# Mac_Project_sch_With_Resistors.net
KiCad netlist of a schematic drawn in EAGLE
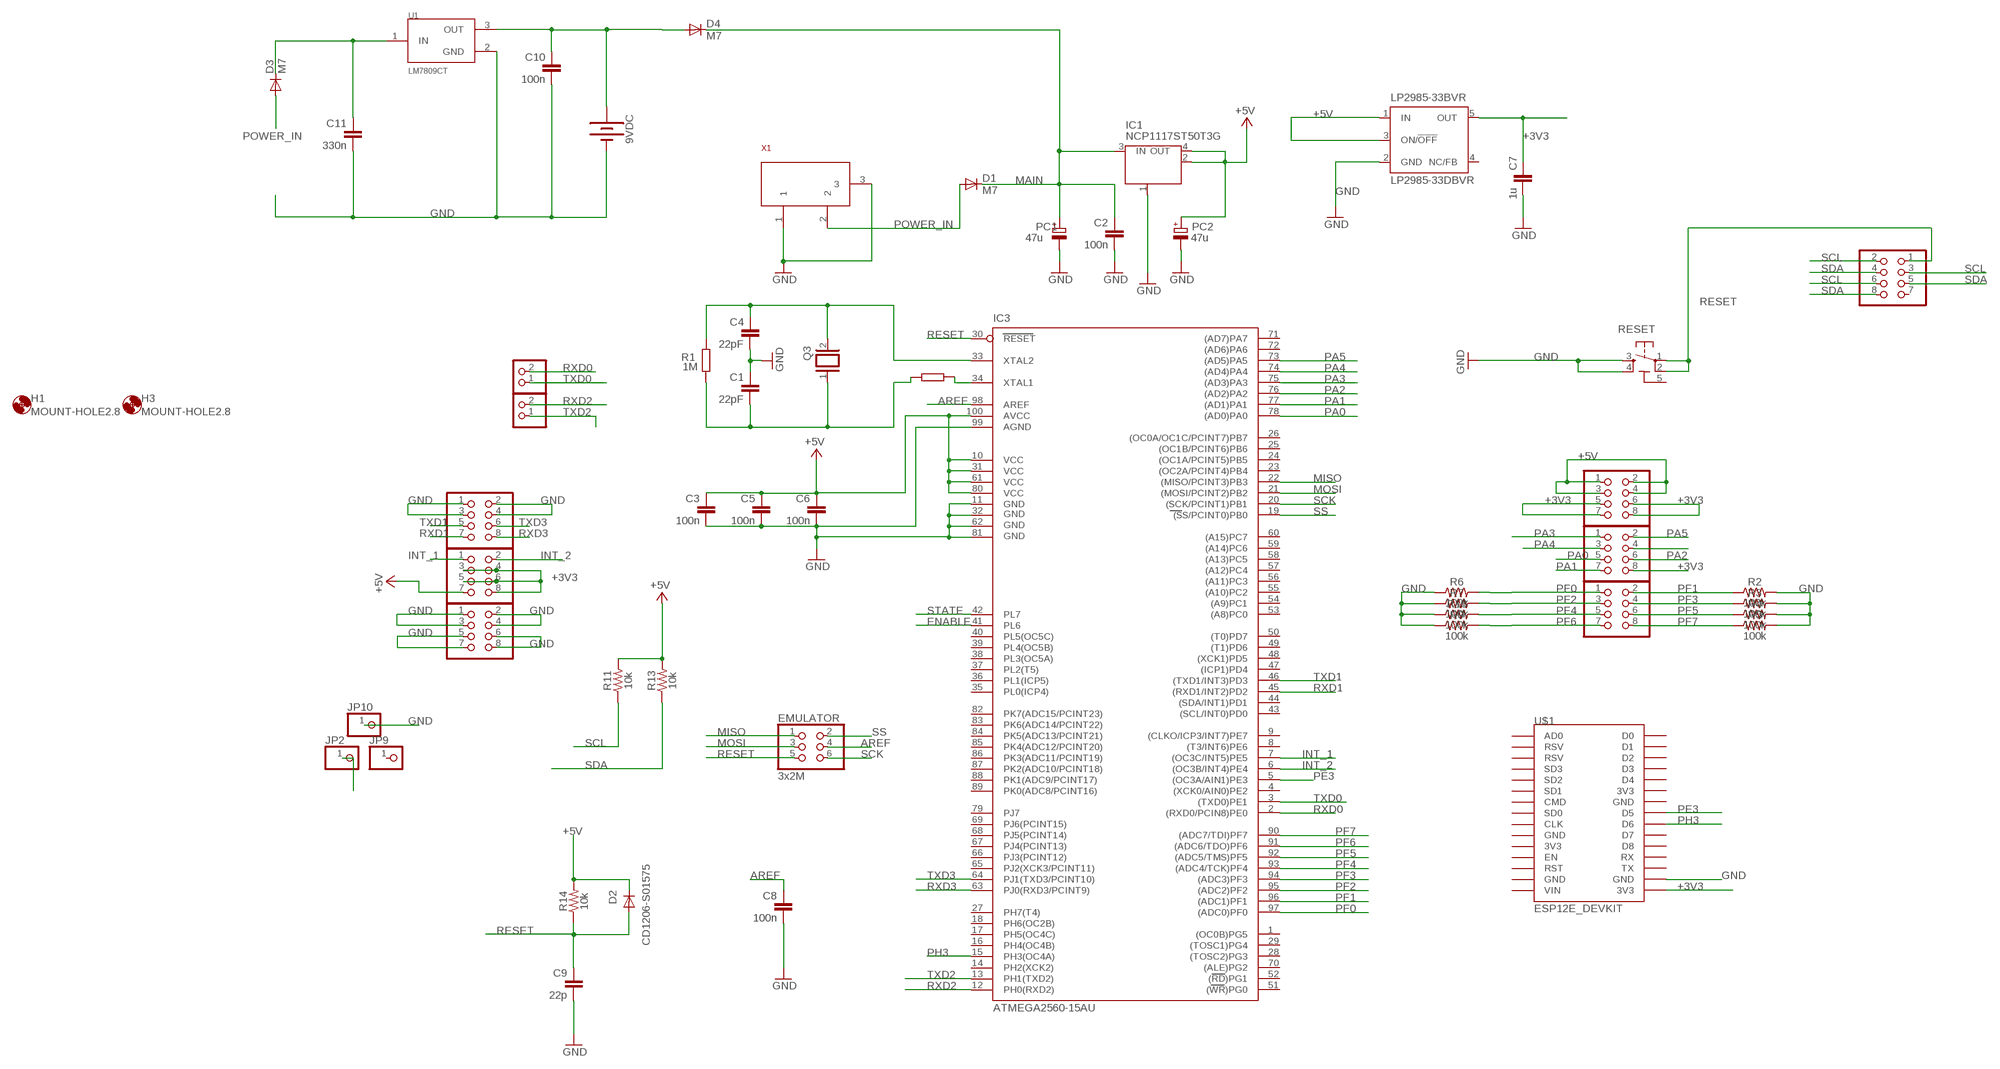
[diagram p0: schematic, sheet 1]

(export (version "E")
  (design (tool "Eeschema 10.0.6"))
  (components
    (comp (ref "1X1")
      (value "1x2")
      (footprint "eagle-import:1X02")
      (libsource (lib "eagle-import") (part "PINHD-1X2"))
    )
    (comp (ref "1X2")
      (value "1x2")
      (footprint "eagle-import:1X02")
      (libsource (lib "eagle-import") (part "PINHD-1X2"))
    )
    (comp (ref "9VDC")
      (value "BATTERY-9V")
      (footprint "eagle-import:BATTCON_9V")
      (libsource (lib "eagle-import") (part "BATTERY-9V"))
    )
    (comp (ref "C1")
      (value "22pF")
      (footprint "eagle-import:C0603-ROUND")
      (libsource (lib "eagle-import") (part "C-EU0603-RND"))
    )
    (comp (ref "C2")
      (value "100n")
      (footprint "eagle-import:C0603-ROUND")
      (libsource (lib "eagle-import") (part "C-EU0603-RND"))
    )
    (comp (ref "C3")
      (value "100n")
      (footprint "eagle-import:C0603-ROUND")
      (libsource (lib "eagle-import") (part "C-EU0603-RND"))
    )
    (comp (ref "C4")
      (value "22pF")
      (footprint "eagle-import:C0603-ROUND")
      (libsource (lib "eagle-import") (part "C-EU0603-RND"))
    )
    (comp (ref "C5")
      (value "100n")
      (footprint "eagle-import:C0603-ROUND")
      (libsource (lib "eagle-import") (part "C-EU0603-RND"))
    )
    (comp (ref "C6")
      (value "100n")
      (footprint "eagle-import:C0603-ROUND")
      (libsource (lib "eagle-import") (part "C-EU0603-RND"))
    )
    (comp (ref "C7")
      (value "1u")
      (footprint "eagle-import:C0603-ROUND")
      (libsource (lib "eagle-import") (part "C-EU0603-RND"))
    )
    (comp (ref "C8")
      (value "100n")
      (footprint "eagle-import:C0603-ROUND")
      (libsource (lib "eagle-import") (part "C-EU0603-RND"))
    )
    (comp (ref "C9")
      (value "22p")
      (footprint "eagle-import:C0603-ROUND")
      (libsource (lib "eagle-import") (part "C-EU0603-RND"))
    )
    (comp (ref "C10")
      (value "100n")
      (footprint "eagle-import:C0603-ROUND")
      (libsource (lib "eagle-import") (part "C-EU0603-RND"))
    )
    (comp (ref "C11")
      (value "330n")
      (footprint "eagle-import:C0603-ROUND")
      (libsource (lib "eagle-import") (part "C-EU0603-RND"))
    )
    (comp (ref "D1")
      (value "M7")
      (footprint "eagle-import:SMB")
      (libsource (lib "eagle-import") (part "DIODE-SMB"))
    )
    (comp (ref "D2")
      (value "CD1206-S01575")
      (footprint "eagle-import:MINIMELF")
      (libsource (lib "eagle-import") (part "DIODE-MINIMELF"))
    )
    (comp (ref "D3")
      (value "M7")
      (footprint "eagle-import:SMB")
      (libsource (lib "eagle-import") (part "DIODE-SMB"))
    )
    (comp (ref "D4")
      (value "M7")
      (footprint "eagle-import:SMB")
      (libsource (lib "eagle-import") (part "DIODE-SMB"))
    )
    (comp (ref "EMULATOR")
      (value "3x2M")
      (footprint "eagle-import:2X03")
      (libsource (lib "eagle-import") (part "PINHD-2X3"))
    )
    (comp (ref "H1")
      (value "MOUNT-HOLE2.8")
      (footprint "eagle-import:2,8")
      (libsource (lib "eagle-import") (part "MOUNT-HOLE2.8"))
    )
    (comp (ref "H3")
      (value "MOUNT-HOLE2.8")
      (footprint "eagle-import:2,8")
      (libsource (lib "eagle-import") (part "MOUNT-HOLE2.8"))
    )
    (comp (ref "IC1")
      (value "NCP1117ST50T3G")
      (footprint "eagle-import:SOT223")
      (libsource (lib "eagle-import") (part "MC33269ST-3.3T3"))
    )
    (comp (ref "IC3")
      (value "ATMEGA2560-15AU")
      (footprint "eagle-import:TQFP100")
      (fields (field (name "PART_NUMBER") "ATMEGA2560-16AU"))
      (libsource (lib "eagle-import") (part "0023_ATMEGA2560-16AU"))
    )
    (comp (ref "JP1")
      (value "PINHD-2X4")
      (footprint "eagle-import:2X04")
      (libsource (lib "eagle-import") (part "PINHD-2X4"))
    )
    (comp (ref "JP2")
      (value "PINHD-1X1")
      (footprint "eagle-import:1X01")
      (libsource (lib "eagle-import") (part "PINHD-1X1"))
    )
    (comp (ref "JP3")
      (value "PINHD-2X4")
      (footprint "eagle-import:2X04")
      (libsource (lib "eagle-import") (part "PINHD-2X4"))
    )
    (comp (ref "JP4")
      (value "PINHD-2X4")
      (footprint "eagle-import:2X04")
      (libsource (lib "eagle-import") (part "PINHD-2X4"))
    )
    (comp (ref "JP5")
      (value "PINHD-2X4")
      (footprint "eagle-import:2X04")
      (libsource (lib "eagle-import") (part "PINHD-2X4"))
    )
    (comp (ref "JP6")
      (value "PINHD-2X4")
      (footprint "eagle-import:2X04")
      (libsource (lib "eagle-import") (part "PINHD-2X4"))
    )
    (comp (ref "JP7")
      (value "PINHD-2X4")
      (footprint "eagle-import:2X04")
      (libsource (lib "eagle-import") (part "PINHD-2X4"))
    )
    (comp (ref "JP8")
      (value "PINHD-2X4")
      (footprint "eagle-import:2X04")
      (libsource (lib "eagle-import") (part "PINHD-2X4"))
    )
    (comp (ref "JP9")
      (value "PINHD-1X1")
      (footprint "eagle-import:1X01")
      (libsource (lib "eagle-import") (part "PINHD-1X1"))
    )
    (comp (ref "JP10")
      (value "PINHD-1X1")
      (footprint "eagle-import:1X01")
      (libsource (lib "eagle-import") (part "PINHD-1X1"))
    )
    (comp (ref "LP2985-33BVR")
      (value "LP2985-33DBVR")
      (footprint "eagle-import:SOT23-DBV")
      (libsource (lib "eagle-import") (part "LP2985-XXDBVR33"))
    )
    (comp (ref "PC1")
      (value "47u")
      (footprint "eagle-import:PANASONIC_D")
      (libsource (lib "eagle-import") (part "CPOL-EUD"))
    )
    (comp (ref "PC2")
      (value "47u")
      (footprint "eagle-import:PANASONIC_D")
      (libsource (lib "eagle-import") (part "CPOL-EUD"))
    )
    (comp (ref "Q3")
      (value "16MHz")
      (footprint "eagle-import:QS")
      (libsource (lib "eagle-import") (part "XTAL/S"))
    )
    (comp (ref "R1")
      (value "1M")
      (footprint "eagle-import:R0603-ROUND")
      (libsource (lib "eagle-import") (part "R-EU_R0603"))
    )
    (comp (ref "R2")
      (value "100k")
      (footprint "eagle-import:0603")
      (libsource (lib "eagle-import") (part "100KOHM-0603-1/10W-1%"))
    )
    (comp (ref "R3")
      (value "100k")
      (footprint "eagle-import:0603")
      (libsource (lib "eagle-import") (part "100KOHM-0603-1/10W-1%"))
    )
    (comp (ref "R4")
      (value "100k")
      (footprint "eagle-import:0603")
      (libsource (lib "eagle-import") (part "100KOHM-0603-1/10W-1%"))
    )
    (comp (ref "R5")
      (value "100k")
      (footprint "eagle-import:0603")
      (libsource (lib "eagle-import") (part "100KOHM-0603-1/10W-1%"))
    )
    (comp (ref "R6")
      (value "100k")
      (footprint "eagle-import:0603")
      (libsource (lib "eagle-import") (part "100KOHM-0603-1/10W-1%"))
    )
    (comp (ref "R7")
      (value "100k")
      (footprint "eagle-import:0603")
      (libsource (lib "eagle-import") (part "100KOHM-0603-1/10W-1%"))
    )
    (comp (ref "R9")
      (value "100k")
      (footprint "eagle-import:0603")
      (libsource (lib "eagle-import") (part "100KOHM-0603-1/10W-1%"))
    )
    (comp (ref "R10")
      (value "100k")
      (footprint "eagle-import:0603")
      (libsource (lib "eagle-import") (part "100KOHM-0603-1/10W-1%"))
    )
    (comp (ref "R11")
      (value "10k")
      (footprint "eagle-import:0603")
      (libsource (lib "eagle-import") (part "10KOHM-0603-1/10W-1%"))
    )
    (comp (ref "R12")
      (value "27O")
      (footprint "eagle-import:R0603-ROUND")
      (libsource (lib "eagle-import") (part "R-EU_R0603"))
    )
    (comp (ref "R13")
      (value "10k")
      (footprint "eagle-import:0603")
      (libsource (lib "eagle-import") (part "10KOHM-0603-1/10W-1%"))
    )
    (comp (ref "R14")
      (value "10k")
      (footprint "eagle-import:0603")
      (libsource (lib "eagle-import") (part "10KOHM-0603-1/10W-1%"))
    )
    (comp (ref "RESET")
      (value "TS42")
      (footprint "eagle-import:TS42")
      (libsource (lib "eagle-import") (part "TS42"))
    )
    (comp (ref "U$1")
      (value "ESP12E_DEVKIT")
      (footprint "eagle-import:ESP12E_DEVKIT")
      (libsource (lib "eagle-import") (part "ESP12E_DEVKIT"))
    )
    (comp (ref "U1")
      (value "LM7809CT")
      (footprint "eagle-import:TO254P470X1016X1879-3P")
      (fields (field (name "MF") "ON Semiconductor"))
      (libsource (lib "eagle-import") (part "LM7809CT"))
    )
    (comp (ref "X1")
      (value "POWERSUPPLY_DC21MMX")
      (footprint "eagle-import:POWERSUPPLY_DC-21MM")
      (libsource (lib "eagle-import") (part "POWERSUPPLY_DC21MMX"))
    )
  )
  (nets
    (net (code "1") (name "+5V") (class "Default")
      (node (ref "C3") (pin "1") (pinfunction "1_1") (pintype "passive"))
      (node (ref "C5") (pin "1") (pinfunction "1_1") (pintype "passive"))
      (node (ref "C6") (pin "1") (pinfunction "1_1") (pintype "passive"))
      (node (ref "D2") (pin "C") (pinfunction "C_C") (pintype "passive"))
      (node (ref "IC1") (pin "2") (pinfunction "OUT_2") (pintype "passive"))
      (node (ref "IC1") (pin "4") (pinfunction "OUT_4") (pintype "passive"))
      (node (ref "IC3") (pin "10") (pinfunction "VCC_10") (pintype "power_in"))
      (node (ref "IC3") (pin "100") (pinfunction "AVCC_100") (pintype "power_in"))
      (node (ref "IC3") (pin "31") (pinfunction "VCC1_31") (pintype "power_in"))
      (node (ref "IC3") (pin "61") (pinfunction "VCC2_61") (pintype "power_in"))
      (node (ref "IC3") (pin "80") (pinfunction "VCC3_80") (pintype "power_in"))
      (node (ref "JP3") (pin "1") (pinfunction "1_1") (pintype "passive"))
      (node (ref "JP3") (pin "2") (pinfunction "2_2") (pintype "passive"))
      (node (ref "JP3") (pin "3") (pinfunction "3_3") (pintype "passive"))
      (node (ref "JP3") (pin "4") (pinfunction "4_4") (pintype "passive"))
      (node (ref "JP7") (pin "7") (pinfunction "7_7") (pintype "passive"))
      (node (ref "LP2985-33BVR") (pin "1") (pinfunction "IN_1") (pintype "input"))
      (node (ref "LP2985-33BVR") (pin "3") (pinfunction "ON/~{OFF}_3") (pintype "input"))
      (node (ref "PC2") (pin "+") (pinfunction "+_+") (pintype "passive"))
      (node (ref "R11") (pin "2") (pinfunction "2_2") (pintype "passive"))
      (node (ref "R13") (pin "2") (pinfunction "2_2") (pintype "passive"))
      (node (ref "R14") (pin "2") (pinfunction "2_2") (pintype "passive"))
    )
    (net (code "2") (name "/+3V3") (class "Default")
      (node (ref "C7") (pin "2") (pinfunction "2_2") (pintype "passive"))
      (node (ref "JP3") (pin "5") (pinfunction "5_5") (pintype "passive"))
      (node (ref "JP3") (pin "6") (pinfunction "6_6") (pintype "passive"))
      (node (ref "JP3") (pin "7") (pinfunction "7_7") (pintype "passive"))
      (node (ref "JP3") (pin "8") (pinfunction "8_8") (pintype "passive"))
      (node (ref "JP4") (pin "8") (pinfunction "8_8") (pintype "passive"))
      (node (ref "JP7") (pin "3") (pinfunction "3_3") (pintype "passive"))
      (node (ref "JP7") (pin "4") (pinfunction "4_4") (pintype "passive"))
      (node (ref "JP7") (pin "5") (pinfunction "5_5") (pintype "passive"))
      (node (ref "JP7") (pin "6") (pinfunction "6_6") (pintype "passive"))
      (node (ref "JP7") (pin "8") (pinfunction "8_8") (pintype "passive"))
      (node (ref "LP2985-33BVR") (pin "5") (pinfunction "OUT_5") (pintype "passive"))
      (node (ref "U$1") (pin "3V3@2") (pinfunction "3V3_3V3@2") (pintype "bidirectional"))
    )
    (net (code "3") (name "/5-GND") (class "Default")
      (node (ref "RESET") (pin "5") (pinfunction "5-GND_5") (pintype "power_in"))
    )
    (net (code "4") (name "/AREF") (class "Default")
      (node (ref "C8") (pin "1") (pinfunction "1_1") (pintype "passive"))
      (node (ref "EMULATOR") (pin "4") (pinfunction "4_4") (pintype "passive"))
      (node (ref "IC3") (pin "98") (pinfunction "AREF_98") (pintype "bidirectional"))
    )
    (net (code "5") (name "/ENABLE") (class "Default")
      (node (ref "IC3") (pin "41") (pinfunction "PL6_41") (pintype "bidirectional"))
    )
    (net (code "6") (name "/INT_1") (class "Default")
      (node (ref "IC3") (pin "7") (pinfunction "(OC3C/INT5)PE5_7") (pintype "bidirectional"))
      (node (ref "JP7") (pin "1") (pinfunction "1_1") (pintype "passive"))
    )
    (net (code "7") (name "/INT_2") (class "Default")
      (node (ref "IC3") (pin "6") (pinfunction "(OC3B/INT4)PE4_6") (pintype "bidirectional"))
      (node (ref "JP7") (pin "2") (pinfunction "2_2") (pintype "passive"))
    )
    (net (code "8") (name "/MAIN") (class "Default")
      (node (ref "C2") (pin "1") (pinfunction "1_1") (pintype "passive"))
      (node (ref "D1") (pin "C") (pinfunction "C_C") (pintype "passive"))
      (node (ref "D4") (pin "C") (pinfunction "C_C") (pintype "passive"))
      (node (ref "IC1") (pin "3") (pinfunction "IN_3") (pintype "input"))
      (node (ref "PC1") (pin "+") (pinfunction "+_+") (pintype "passive"))
    )
    (net (code "9") (name "/MISO") (class "Default")
      (node (ref "EMULATOR") (pin "1") (pinfunction "1_1") (pintype "passive"))
      (node (ref "IC3") (pin "22") (pinfunction "(MISO/PCINT3)PB3_22") (pintype "bidirectional"))
    )
    (net (code "10") (name "/MOSI") (class "Default")
      (node (ref "EMULATOR") (pin "3") (pinfunction "3_3") (pintype "passive"))
      (node (ref "IC3") (pin "21") (pinfunction "(MOSI/PCINT2)PB2_21") (pintype "bidirectional"))
    )
    (net (code "11") (name "/PA0") (class "Default")
      (node (ref "IC3") (pin "78") (pinfunction "(AD0)PA0_78") (pintype "bidirectional"))
      (node (ref "JP4") (pin "5") (pinfunction "5_5") (pintype "passive"))
    )
    (net (code "12") (name "/PA1") (class "Default")
      (node (ref "IC3") (pin "77") (pinfunction "(AD1)PA1_77") (pintype "bidirectional"))
      (node (ref "JP4") (pin "7") (pinfunction "7_7") (pintype "passive"))
    )
    (net (code "13") (name "/PA2") (class "Default")
      (node (ref "IC3") (pin "76") (pinfunction "(AD2)PA2_76") (pintype "bidirectional"))
      (node (ref "JP4") (pin "6") (pinfunction "6_6") (pintype "passive"))
    )
    (net (code "14") (name "/PA3") (class "Default")
      (node (ref "IC3") (pin "75") (pinfunction "(AD3)PA3_75") (pintype "bidirectional"))
      (node (ref "JP4") (pin "1") (pinfunction "1_1") (pintype "passive"))
    )
    (net (code "15") (name "/PA4") (class "Default")
      (node (ref "IC3") (pin "74") (pinfunction "(AD4)PA4_74") (pintype "bidirectional"))
      (node (ref "JP4") (pin "3") (pinfunction "3_3") (pintype "passive"))
    )
    (net (code "16") (name "/PA5") (class "Default")
      (node (ref "IC3") (pin "73") (pinfunction "(AD5)PA5_73") (pintype "bidirectional"))
      (node (ref "JP4") (pin "2") (pinfunction "2_2") (pintype "passive"))
    )
    (net (code "17") (name "/PE3") (class "Default")
      (node (ref "IC3") (pin "5") (pinfunction "(OC3A/AIN1)PE3_5") (pintype "bidirectional"))
      (node (ref "U$1") (pin "D5") (pinfunction "D5_D5") (pintype "bidirectional"))
    )
    (net (code "18") (name "/PF0") (class "Default")
      (node (ref "IC3") (pin "97") (pinfunction "(ADC0)PF0_97") (pintype "bidirectional"))
      (node (ref "JP8") (pin "1") (pinfunction "1_1") (pintype "passive"))
      (node (ref "R6") (pin "2") (pinfunction "2_2") (pintype "passive"))
    )
    (net (code "19") (name "/PF1") (class "Default")
      (node (ref "IC3") (pin "96") (pinfunction "(ADC1)PF1_96") (pintype "bidirectional"))
      (node (ref "JP8") (pin "2") (pinfunction "2_2") (pintype "passive"))
      (node (ref "R2") (pin "1") (pinfunction "1_1") (pintype "passive"))
    )
    (net (code "20") (name "/PF2") (class "Default")
      (node (ref "IC3") (pin "95") (pinfunction "(ADC2)PF2_95") (pintype "bidirectional"))
      (node (ref "JP8") (pin "3") (pinfunction "3_3") (pintype "passive"))
      (node (ref "R7") (pin "2") (pinfunction "2_2") (pintype "passive"))
    )
    (net (code "21") (name "/PF3") (class "Default")
      (node (ref "IC3") (pin "94") (pinfunction "(ADC3)PF3_94") (pintype "bidirectional"))
      (node (ref "JP8") (pin "4") (pinfunction "4_4") (pintype "passive"))
      (node (ref "R3") (pin "1") (pinfunction "1_1") (pintype "passive"))
    )
    (net (code "22") (name "/PF4") (class "Default")
      (node (ref "IC3") (pin "93") (pinfunction "(ADC4/TCK)PF4_93") (pintype "bidirectional"))
      (node (ref "JP8") (pin "5") (pinfunction "5_5") (pintype "passive"))
      (node (ref "R10") (pin "2") (pinfunction "2_2") (pintype "passive"))
    )
    (net (code "23") (name "/PF5") (class "Default")
      (node (ref "IC3") (pin "92") (pinfunction "(ADC5/TMS)PF5_92") (pintype "bidirectional"))
      (node (ref "JP8") (pin "6") (pinfunction "6_6") (pintype "passive"))
      (node (ref "R4") (pin "1") (pinfunction "1_1") (pintype "passive"))
    )
    (net (code "24") (name "/PF6") (class "Default")
      (node (ref "IC3") (pin "91") (pinfunction "(ADC6/TDO)PF6_91") (pintype "bidirectional"))
      (node (ref "JP8") (pin "7") (pinfunction "7_7") (pintype "passive"))
      (node (ref "R9") (pin "2") (pinfunction "2_2") (pintype "passive"))
    )
    (net (code "25") (name "/PF7") (class "Default")
      (node (ref "IC3") (pin "90") (pinfunction "(ADC7/TDI)PF7_90") (pintype "bidirectional"))
      (node (ref "JP8") (pin "8") (pinfunction "8_8") (pintype "passive"))
      (node (ref "R5") (pin "1") (pinfunction "1_1") (pintype "passive"))
    )
    (net (code "26") (name "/PH3") (class "Default")
      (node (ref "IC3") (pin "15") (pinfunction "PH3(OC4A)_15") (pintype "bidirectional"))
      (node (ref "U$1") (pin "D6") (pinfunction "D6_D6") (pintype "bidirectional"))
    )
    (net (code "27") (name "/POWER_IN") (class "Default")
      (node (ref "D1") (pin "A") (pinfunction "A_A") (pintype "passive"))
      (node (ref "D3") (pin "A") (pinfunction "A_A") (pintype "passive"))
      (node (ref "X1") (pin "2") (pinfunction "2_2") (pintype "power_in"))
    )
    (net (code "28") (name "/RESET") (class "Default")
      (node (ref "C9") (pin "1") (pinfunction "1_1") (pintype "passive"))
      (node (ref "D2") (pin "A") (pinfunction "A_A") (pintype "passive"))
      (node (ref "EMULATOR") (pin "5") (pinfunction "5_5") (pintype "passive"))
      (node (ref "IC3") (pin "30") (pinfunction "RESET_30") (pintype "input"))
      (node (ref "JP5") (pin "1") (pinfunction "1_1") (pintype "passive"))
      (node (ref "R14") (pin "1") (pinfunction "1_1") (pintype "passive"))
      (node (ref "RESET") (pin "1") (pinfunction "1_1") (pintype "passive"))
      (node (ref "RESET") (pin "2") (pinfunction "2_2") (pintype "passive"))
    )
    (net (code "29") (name "/RXD0") (class "Default")
      (node (ref "1X2") (pin "2") (pinfunction "2_2") (pintype "passive"))
      (node (ref "IC3") (pin "2") (pinfunction "(RXD0/PCIN8)PE0_2") (pintype "bidirectional"))
    )
    (net (code "30") (name "/RXD1") (class "Default")
      (node (ref "IC3") (pin "45") (pinfunction "(RXD1/INT2)PD2_45") (pintype "bidirectional"))
      (node (ref "JP6") (pin "7") (pinfunction "7_7") (pintype "passive"))
    )
    (net (code "31") (name "/RXD2") (class "Default")
      (node (ref "1X1") (pin "2") (pinfunction "2_2") (pintype "passive"))
      (node (ref "IC3") (pin "12") (pinfunction "PH0(RXD2)_12") (pintype "bidirectional"))
    )
    (net (code "32") (name "/RXD3") (class "Default")
      (node (ref "IC3") (pin "63") (pinfunction "PJ0(RXD3/PCINT9)_63") (pintype "bidirectional"))
      (node (ref "JP6") (pin "8") (pinfunction "8_8") (pintype "passive"))
    )
    (net (code "33") (name "/SCK") (class "Default")
      (node (ref "EMULATOR") (pin "6") (pinfunction "6_6") (pintype "passive"))
      (node (ref "IC3") (pin "20") (pinfunction "(SCK/PCINT1)PB1_20") (pintype "bidirectional"))
    )
    (net (code "34") (name "/SCL") (class "Default")
      (node (ref "JP5") (pin "2") (pinfunction "2_2") (pintype "passive"))
      (node (ref "JP5") (pin "3") (pinfunction "3_3") (pintype "passive"))
      (node (ref "JP5") (pin "6") (pinfunction "6_6") (pintype "passive"))
      (node (ref "R11") (pin "1") (pinfunction "1_1") (pintype "passive"))
    )
    (net (code "35") (name "/SDA") (class "Default")
      (node (ref "JP5") (pin "4") (pinfunction "4_4") (pintype "passive"))
      (node (ref "JP5") (pin "5") (pinfunction "5_5") (pintype "passive"))
      (node (ref "JP5") (pin "8") (pinfunction "8_8") (pintype "passive"))
      (node (ref "R13") (pin "1") (pinfunction "1_1") (pintype "passive"))
    )
    (net (code "36") (name "/SS") (class "Default")
      (node (ref "EMULATOR") (pin "2") (pinfunction "2_2") (pintype "passive"))
      (node (ref "IC3") (pin "19") (pinfunction "(SS/PCINT0)PB0_19") (pintype "bidirectional"))
    )
    (net (code "37") (name "/STATE") (class "Default")
      (node (ref "IC3") (pin "42") (pinfunction "PL7_42") (pintype "bidirectional"))
    )
    (net (code "38") (name "/TXD0") (class "Default")
      (node (ref "1X2") (pin "1") (pinfunction "1_1") (pintype "passive"))
      (node (ref "IC3") (pin "3") (pinfunction "(TXD0)PE1_3") (pintype "bidirectional"))
    )
    (net (code "39") (name "/TXD1") (class "Default")
      (node (ref "IC3") (pin "46") (pinfunction "(TXD1/INT3)PD3_46") (pintype "bidirectional"))
      (node (ref "JP6") (pin "5") (pinfunction "5_5") (pintype "passive"))
    )
    (net (code "40") (name "/TXD2") (class "Default")
      (node (ref "1X1") (pin "1") (pinfunction "1_1") (pintype "passive"))
      (node (ref "IC3") (pin "13") (pinfunction "PH1(TXD2)_13") (pintype "bidirectional"))
    )
    (net (code "41") (name "/TXD3") (class "Default")
      (node (ref "IC3") (pin "64") (pinfunction "PJ1(TXD3/PCINT10)_64") (pintype "bidirectional"))
      (node (ref "JP6") (pin "6") (pinfunction "6_6") (pintype "passive"))
    )
    (net (code "42") (name "GND") (class "Default")
      (node (ref "9VDC") (pin "-") (pinfunction "-_-") (pintype "power_in"))
      (node (ref "C1") (pin "1") (pinfunction "1_1") (pintype "passive"))
      (node (ref "C10") (pin "2") (pinfunction "2_2") (pintype "passive"))
      (node (ref "C11") (pin "2") (pinfunction "2_2") (pintype "passive"))
      (node (ref "C2") (pin "2") (pinfunction "2_2") (pintype "passive"))
      (node (ref "C3") (pin "2") (pinfunction "2_2") (pintype "passive"))
      (node (ref "C4") (pin "2") (pinfunction "2_2") (pintype "passive"))
      (node (ref "C5") (pin "2") (pinfunction "2_2") (pintype "passive"))
      (node (ref "C6") (pin "2") (pinfunction "2_2") (pintype "passive"))
      (node (ref "C7") (pin "1") (pinfunction "1_1") (pintype "passive"))
      (node (ref "C8") (pin "2") (pinfunction "2_2") (pintype "passive"))
      (node (ref "C9") (pin "2") (pinfunction "2_2") (pintype "passive"))
      (node (ref "IC1") (pin "1") (pinfunction "GND/ADJ_1") (pintype "input"))
      (node (ref "IC3") (pin "11") (pinfunction "GND_11") (pintype "power_in"))
      (node (ref "IC3") (pin "32") (pinfunction "GND1_32") (pintype "power_in"))
      (node (ref "IC3") (pin "62") (pinfunction "GND2_62") (pintype "power_in"))
      (node (ref "IC3") (pin "81") (pinfunction "GND3_81") (pintype "power_in"))
      (node (ref "IC3") (pin "99") (pinfunction "AGND_99") (pintype "power_in"))
      (node (ref "JP1") (pin "1") (pinfunction "1_1") (pintype "passive"))
      (node (ref "JP1") (pin "2") (pinfunction "2_2") (pintype "passive"))
      (node (ref "JP1") (pin "3") (pinfunction "3_3") (pintype "passive"))
      (node (ref "JP1") (pin "4") (pinfunction "4_4") (pintype "passive"))
      (node (ref "JP1") (pin "5") (pinfunction "5_5") (pintype "passive"))
      (node (ref "JP1") (pin "6") (pinfunction "6_6") (pintype "passive"))
      (node (ref "JP1") (pin "7") (pinfunction "7_7") (pintype "passive"))
      (node (ref "JP1") (pin "8") (pinfunction "8_8") (pintype "passive"))
      (node (ref "JP10") (pin "1") (pinfunction "1_1") (pintype "passive"))
      (node (ref "JP4") (pin "4") (pinfunction "4_4") (pintype "passive"))
      (node (ref "JP6") (pin "1") (pinfunction "1_1") (pintype "passive"))
      (node (ref "JP6") (pin "2") (pinfunction "2_2") (pintype "passive"))
      (node (ref "JP6") (pin "3") (pinfunction "3_3") (pintype "passive"))
      (node (ref "JP6") (pin "4") (pinfunction "4_4") (pintype "passive"))
      (node (ref "LP2985-33BVR") (pin "2") (pinfunction "GND_2") (pintype "power_in"))
      (node (ref "PC1") (pin "-") (pinfunction "-_-") (pintype "passive"))
      (node (ref "PC2") (pin "-") (pinfunction "-_-") (pintype "passive"))
      (node (ref "R10") (pin "1") (pinfunction "1_1") (pintype "passive"))
      (node (ref "R2") (pin "2") (pinfunction "2_2") (pintype "passive"))
      (node (ref "R3") (pin "2") (pinfunction "2_2") (pintype "passive"))
      (node (ref "R4") (pin "2") (pinfunction "2_2") (pintype "passive"))
      (node (ref "R5") (pin "2") (pinfunction "2_2") (pintype "passive"))
      (node (ref "R6") (pin "1") (pinfunction "1_1") (pintype "passive"))
      (node (ref "R7") (pin "1") (pinfunction "1_1") (pintype "passive"))
      (node (ref "R9") (pin "1") (pinfunction "1_1") (pintype "passive"))
      (node (ref "RESET") (pin "3") (pinfunction "3_3") (pintype "passive"))
      (node (ref "RESET") (pin "4") (pinfunction "4_4") (pintype "passive"))
      (node (ref "U$1") (pin "GND@3") (pinfunction "GND_GND@3") (pintype "bidirectional"))
      (node (ref "U1") (pin "2") (pinfunction "GND_2") (pintype "power_in"))
      (node (ref "X1") (pin "1") (pinfunction "1_1") (pintype "power_in"))
      (node (ref "X1") (pin "3") (pinfunction "3_3") (pintype "power_in"))
    )
    (net (code "43") (name "Net-(C1-Pad2)") (class "Default")
      (node (ref "C1") (pin "2") (pinfunction "2_2") (pintype "passive"))
      (node (ref "Q3") (pin "1") (pinfunction "1_1") (pintype "passive"))
      (node (ref "R1") (pin "1") (pinfunction "1_1") (pintype "passive"))
      (node (ref "R12") (pin "1") (pinfunction "1_1") (pintype "passive"))
    )
    (net (code "44") (name "Net-(IC3-XTAL1)") (class "Default")
      (node (ref "IC3") (pin "34") (pinfunction "XTAL1_34") (pintype "input"))
      (node (ref "R12") (pin "2") (pinfunction "2_2") (pintype "passive"))
    )
    (net (code "45") (name "Net-(IC3-XTAL2)") (class "Default")
      (node (ref "C4") (pin "1") (pinfunction "1_1") (pintype "passive"))
      (node (ref "IC3") (pin "33") (pinfunction "XTAL2_33") (pintype "output"))
      (node (ref "Q3") (pin "2") (pinfunction "2_2") (pintype "passive"))
      (node (ref "R1") (pin "2") (pinfunction "2_2") (pintype "passive"))
    )
    (net (code "46") (name "Net-(U1-IN)") (class "Default")
      (node (ref "C11") (pin "1") (pinfunction "1_1") (pintype "passive"))
      (node (ref "D3") (pin "C") (pinfunction "C_C") (pintype "passive"))
      (node (ref "U1") (pin "1") (pinfunction "IN_1") (pintype "input"))
    )
    (net (code "47") (name "Net-(U1-OUT)") (class "Default")
      (node (ref "9VDC") (pin "+") (pinfunction "+_+") (pintype "power_in"))
      (node (ref "C10") (pin "1") (pinfunction "1_1") (pintype "passive"))
      (node (ref "D4") (pin "A") (pinfunction "A_A") (pintype "passive"))
      (node (ref "U1") (pin "3") (pinfunction "OUT_3") (pintype "output"))
    )
    (net (code "48") (name "unconnected-(IC3-(A8)PC0-Pad53)") (class "Default")
      (node (ref "IC3") (pin "53") (pinfunction "(A8)PC0_53") (pintype "bidirectional"))
    )
    (net (code "49") (name "unconnected-(IC3-(A9)PC1-Pad54)") (class "Default")
      (node (ref "IC3") (pin "54") (pinfunction "(A9)PC1_54") (pintype "bidirectional"))
    )
    (net (code "50") (name "unconnected-(IC3-(A10)PC2-Pad55)") (class "Default")
      (node (ref "IC3") (pin "55") (pinfunction "(A10)PC2_55") (pintype "bidirectional"))
    )
    (net (code "51") (name "unconnected-(IC3-(A11)PC3-Pad56)") (class "Default")
      (node (ref "IC3") (pin "56") (pinfunction "(A11)PC3_56") (pintype "bidirectional"))
    )
    (net (code "52") (name "unconnected-(IC3-(A12)PC4-Pad57)") (class "Default")
      (node (ref "IC3") (pin "57") (pinfunction "(A12)PC4_57") (pintype "bidirectional"))
    )
    (net (code "53") (name "unconnected-(IC3-(A13)PC5-Pad58)") (class "Default")
      (node (ref "IC3") (pin "58") (pinfunction "(A13)PC5_58") (pintype "bidirectional"))
    )
    (net (code "54") (name "unconnected-(IC3-(A14)PC6-Pad59)") (class "Default")
      (node (ref "IC3") (pin "59") (pinfunction "(A14)PC6_59") (pintype "bidirectional"))
    )
    (net (code "55") (name "unconnected-(IC3-(A15)PC7-Pad60)") (class "Default")
      (node (ref "IC3") (pin "60") (pinfunction "(A15)PC7_60") (pintype "bidirectional"))
    )
    (net (code "56") (name "unconnected-(IC3-(AD6)PA6-Pad72)") (class "Default")
      (node (ref "IC3") (pin "72") (pinfunction "(AD6)PA6_72") (pintype "bidirectional"))
    )
    (net (code "57") (name "unconnected-(IC3-(AD7)PA7-Pad71)") (class "Default")
      (node (ref "IC3") (pin "71") (pinfunction "(AD7)PA7_71") (pintype "bidirectional"))
    )
    (net (code "58") (name "unconnected-(IC3-(ALE)PG2-Pad70)") (class "Default")
      (node (ref "IC3") (pin "70") (pinfunction "(ALE)PG2_70") (pintype "bidirectional"))
    )
    (net (code "59") (name "unconnected-(IC3-(CLKO{slash}ICP3{slash}INT7)PE7-Pad9)") (class "Default")
      (node (ref "IC3") (pin "9") (pinfunction "(CLKO/ICP3/INT7)PE7_9") (pintype "bidirectional"))
    )
    (net (code "60") (name "unconnected-(IC3-(ICP1)PD4-Pad47)") (class "Default")
      (node (ref "IC3") (pin "47") (pinfunction "(ICP1)PD4_47") (pintype "bidirectional"))
    )
    (net (code "61") (name "unconnected-(IC3-(OC0A{slash}OC1C{slash}PCINT7)PB7-Pad26)") (class "Default")
      (node (ref "IC3") (pin "26") (pinfunction "(OC0A/OC1C/PCINT7)PB7_26") (pintype "bidirectional"))
    )
    (net (code "62") (name "unconnected-(IC3-(OC0B)PG5-Pad1)") (class "Default")
      (node (ref "IC3") (pin "1") (pinfunction "(OC0B)PG5_1") (pintype "bidirectional"))
    )
    (net (code "63") (name "unconnected-(IC3-(OC1A{slash}PCINT5)PB5-Pad24)") (class "Default")
      (node (ref "IC3") (pin "24") (pinfunction "(OC1A/PCINT5)PB5_24") (pintype "bidirectional"))
    )
    (net (code "64") (name "unconnected-(IC3-(OC1B{slash}PCINT6)PB6-Pad25)") (class "Default")
      (node (ref "IC3") (pin "25") (pinfunction "(OC1B/PCINT6)PB6_25") (pintype "bidirectional"))
    )
    (net (code "65") (name "unconnected-(IC3-(OC2A{slash}PCINT4)PB4-Pad23)") (class "Default")
      (node (ref "IC3") (pin "23") (pinfunction "(OC2A/PCINT4)PB4_23") (pintype "bidirectional"))
    )
    (net (code "66") (name "unconnected-(IC3-(RD)PG1-Pad52)") (class "Default")
      (node (ref "IC3") (pin "52") (pinfunction "(RD)PG1_52") (pintype "bidirectional"))
    )
    (net (code "67") (name "unconnected-(IC3-(SCL{slash}INT0)PD0-Pad43)") (class "Default")
      (node (ref "IC3") (pin "43") (pinfunction "(SCL/INT0)PD0_43") (pintype "bidirectional"))
    )
    (net (code "68") (name "unconnected-(IC3-(SDA{slash}INT1)PD1-Pad44)") (class "Default")
      (node (ref "IC3") (pin "44") (pinfunction "(SDA/INT1)PD1_44") (pintype "bidirectional"))
    )
    (net (code "69") (name "unconnected-(IC3-(T0)PD7-Pad50)") (class "Default")
      (node (ref "IC3") (pin "50") (pinfunction "(T0)PD7_50") (pintype "bidirectional"))
    )
    (net (code "70") (name "unconnected-(IC3-(T1)PD6-Pad49)") (class "Default")
      (node (ref "IC3") (pin "49") (pinfunction "(T1)PD6_49") (pintype "bidirectional"))
    )
    (net (code "71") (name "unconnected-(IC3-(T3{slash}INT6)PE6-Pad8)") (class "Default")
      (node (ref "IC3") (pin "8") (pinfunction "(T3/INT6)PE6_8") (pintype "bidirectional"))
    )
    (net (code "72") (name "unconnected-(IC3-(TOSC1)PG4-Pad29)") (class "Default")
      (node (ref "IC3") (pin "29") (pinfunction "(TOSC1)PG4_29") (pintype "bidirectional"))
    )
    (net (code "73") (name "unconnected-(IC3-(TOSC2)PG3-Pad28)") (class "Default")
      (node (ref "IC3") (pin "28") (pinfunction "(TOSC2)PG3_28") (pintype "bidirectional"))
    )
    (net (code "74") (name "unconnected-(IC3-(WR)PG0-Pad51)") (class "Default")
      (node (ref "IC3") (pin "51") (pinfunction "(WR)PG0_51") (pintype "bidirectional"))
    )
    (net (code "75") (name "unconnected-(IC3-(XCK0{slash}AIN0)PE2-Pad4)") (class "Default")
      (node (ref "IC3") (pin "4") (pinfunction "(XCK0/AIN0)PE2_4") (pintype "bidirectional"))
    )
    (net (code "76") (name "unconnected-(IC3-(XCK1)PD5-Pad48)") (class "Default")
      (node (ref "IC3") (pin "48") (pinfunction "(XCK1)PD5_48") (pintype "bidirectional"))
    )
    (net (code "77") (name "unconnected-(IC3-PH2(XCK2)-Pad14)") (class "Default")
      (node (ref "IC3") (pin "14") (pinfunction "PH2(XCK2)_14") (pintype "bidirectional"))
    )
    (net (code "78") (name "unconnected-(IC3-PH4(OC4B)-Pad16)") (class "Default")
      (node (ref "IC3") (pin "16") (pinfunction "PH4(OC4B)_16") (pintype "bidirectional"))
    )
    (net (code "79") (name "unconnected-(IC3-PH5(OC4C)-Pad17)") (class "Default")
      (node (ref "IC3") (pin "17") (pinfunction "PH5(OC4C)_17") (pintype "bidirectional"))
    )
    (net (code "80") (name "unconnected-(IC3-PH6(OC2B)-Pad18)") (class "Default")
      (node (ref "IC3") (pin "18") (pinfunction "PH6(OC2B)_18") (pintype "bidirectional"))
    )
    (net (code "81") (name "unconnected-(IC3-PH7(T4)-Pad27)") (class "Default")
      (node (ref "IC3") (pin "27") (pinfunction "PH7(T4)_27") (pintype "bidirectional"))
    )
    (net (code "82") (name "unconnected-(IC3-PJ2(XCK3{slash}PCINT11)-Pad65)") (class "Default")
      (node (ref "IC3") (pin "65") (pinfunction "PJ2(XCK3/PCINT11)_65") (pintype "bidirectional"))
    )
    (net (code "83") (name "unconnected-(IC3-PJ3(PCINT12)-Pad66)") (class "Default")
      (node (ref "IC3") (pin "66") (pinfunction "PJ3(PCINT12)_66") (pintype "bidirectional"))
    )
    (net (code "84") (name "unconnected-(IC3-PJ4(PCINT13)-Pad67)") (class "Default")
      (node (ref "IC3") (pin "67") (pinfunction "PJ4(PCINT13)_67") (pintype "bidirectional"))
    )
    (net (code "85") (name "unconnected-(IC3-PJ5(PCINT14)-Pad68)") (class "Default")
      (node (ref "IC3") (pin "68") (pinfunction "PJ5(PCINT14)_68") (pintype "bidirectional"))
    )
    (net (code "86") (name "unconnected-(IC3-PJ6(PCINT15)-Pad69)") (class "Default")
      (node (ref "IC3") (pin "69") (pinfunction "PJ6(PCINT15)_69") (pintype "bidirectional"))
    )
    (net (code "87") (name "unconnected-(IC3-PJ7-Pad79)") (class "Default")
      (node (ref "IC3") (pin "79") (pinfunction "PJ7_79") (pintype "bidirectional"))
    )
    (net (code "88") (name "unconnected-(IC3-PK0(ADC8{slash}PCINT16)-Pad89)") (class "Default")
      (node (ref "IC3") (pin "89") (pinfunction "PK0(ADC8/PCINT16)_89") (pintype "bidirectional"))
    )
    (net (code "89") (name "unconnected-(IC3-PK1(ADC9{slash}PCINT17)-Pad88)") (class "Default")
      (node (ref "IC3") (pin "88") (pinfunction "PK1(ADC9/PCINT17)_88") (pintype "bidirectional"))
    )
    (net (code "90") (name "unconnected-(IC3-PK2(ADC10{slash}PCINT18)-Pad87)") (class "Default")
      (node (ref "IC3") (pin "87") (pinfunction "PK2(ADC10/PCINT18)_87") (pintype "bidirectional"))
    )
    (net (code "91") (name "unconnected-(IC3-PK3(ADC11{slash}PCINT19)-Pad86)") (class "Default")
      (node (ref "IC3") (pin "86") (pinfunction "PK3(ADC11/PCINT19)_86") (pintype "bidirectional"))
    )
    (net (code "92") (name "unconnected-(IC3-PK4(ADC12{slash}PCINT20)-Pad85)") (class "Default")
      (node (ref "IC3") (pin "85") (pinfunction "PK4(ADC12/PCINT20)_85") (pintype "bidirectional"))
    )
    (net (code "93") (name "unconnected-(IC3-PK5(ADC13{slash}PCINT21)-Pad84)") (class "Default")
      (node (ref "IC3") (pin "84") (pinfunction "PK5(ADC13/PCINT21)_84") (pintype "bidirectional"))
    )
    (net (code "94") (name "unconnected-(IC3-PK6(ADC14{slash}PCINT22)-Pad83)") (class "Default")
      (node (ref "IC3") (pin "83") (pinfunction "PK6(ADC14/PCINT22)_83") (pintype "bidirectional"))
    )
    (net (code "95") (name "unconnected-(IC3-PK7(ADC15{slash}PCINT23)-Pad82)") (class "Default")
      (node (ref "IC3") (pin "82") (pinfunction "PK7(ADC15/PCINT23)_82") (pintype "bidirectional"))
    )
    (net (code "96") (name "unconnected-(IC3-PL0(ICP4)-Pad35)") (class "Default")
      (node (ref "IC3") (pin "35") (pinfunction "PL0(ICP4)_35") (pintype "bidirectional"))
    )
    (net (code "97") (name "unconnected-(IC3-PL1(ICP5)-Pad36)") (class "Default")
      (node (ref "IC3") (pin "36") (pinfunction "PL1(ICP5)_36") (pintype "bidirectional"))
    )
    (net (code "98") (name "unconnected-(IC3-PL2(T5)-Pad37)") (class "Default")
      (node (ref "IC3") (pin "37") (pinfunction "PL2(T5)_37") (pintype "bidirectional"))
    )
    (net (code "99") (name "unconnected-(IC3-PL3(OC5A)-Pad38)") (class "Default")
      (node (ref "IC3") (pin "38") (pinfunction "PL3(OC5A)_38") (pintype "bidirectional"))
    )
    (net (code "100") (name "unconnected-(IC3-PL4(OC5B)-Pad39)") (class "Default")
      (node (ref "IC3") (pin "39") (pinfunction "PL4(OC5B)_39") (pintype "bidirectional"))
    )
    (net (code "101") (name "unconnected-(IC3-PL5(OC5C)-Pad40)") (class "Default")
      (node (ref "IC3") (pin "40") (pinfunction "PL5(OC5C)_40") (pintype "bidirectional"))
    )
    (net (code "102") (name "unconnected-(JP2-Pad1)") (class "Default")
      (node (ref "JP2") (pin "1") (pinfunction "1_1") (pintype "passive"))
    )
    (net (code "103") (name "unconnected-(JP5-Pad7)") (class "Default")
      (node (ref "JP5") (pin "7") (pinfunction "7_7") (pintype "passive"))
    )
    (net (code "104") (name "unconnected-(JP9-Pad1)") (class "Default")
      (node (ref "JP9") (pin "1") (pinfunction "1_1") (pintype "passive"))
    )
    (net (code "105") (name "unconnected-(LP2985-33BVR-NC{slash}FB-Pad4)") (class "Default")
      (node (ref "LP2985-33BVR") (pin "4") (pinfunction "NC/FB_4") (pintype "passive"))
    )
    (net (code "106") (name "unconnected-(U$1-3V3-Pad3V3@0)") (class "Default")
      (node (ref "U$1") (pin "3V3@0") (pinfunction "3V3_3V3@0") (pintype "bidirectional"))
    )
    (net (code "107") (name "unconnected-(U$1-3V3-Pad3V3@1)") (class "Default")
      (node (ref "U$1") (pin "3V3@1") (pinfunction "3V3_3V3@1") (pintype "bidirectional"))
    )
    (net (code "108") (name "unconnected-(U$1-GND-PadGND@0)") (class "Default")
      (node (ref "U$1") (pin "GND@0") (pinfunction "GND_GND@0") (pintype "bidirectional"))
    )
    (net (code "109") (name "unconnected-(U$1-GND-PadGND@1)") (class "Default")
      (node (ref "U$1") (pin "GND@1") (pinfunction "GND_GND@1") (pintype "bidirectional"))
    )
    (net (code "110") (name "unconnected-(U$1-GND-PadGND@2)") (class "Default")
      (node (ref "U$1") (pin "GND@2") (pinfunction "GND_GND@2") (pintype "bidirectional"))
    )
    (net (code "111") (name "unconnected-(U$1-PadAD0)") (class "Default")
      (node (ref "U$1") (pin "AD0") (pinfunction "AD0_AD0") (pintype "bidirectional"))
    )
    (net (code "112") (name "unconnected-(U$1-PadCLK)") (class "Default")
      (node (ref "U$1") (pin "CLK") (pinfunction "CLK_CLK") (pintype "bidirectional"))
    )
    (net (code "113") (name "unconnected-(U$1-PadCMD)") (class "Default")
      (node (ref "U$1") (pin "CMD") (pinfunction "CMD_CMD") (pintype "bidirectional"))
    )
    (net (code "114") (name "unconnected-(U$1-PadD0)") (class "Default")
      (node (ref "U$1") (pin "D0") (pinfunction "D0_D0") (pintype "bidirectional"))
    )
    (net (code "115") (name "unconnected-(U$1-PadD1)") (class "Default")
      (node (ref "U$1") (pin "D1") (pinfunction "D1_D1") (pintype "bidirectional"))
    )
    (net (code "116") (name "unconnected-(U$1-PadD2)") (class "Default")
      (node (ref "U$1") (pin "D2") (pinfunction "D2_D2") (pintype "bidirectional"))
    )
    (net (code "117") (name "unconnected-(U$1-PadD3)") (class "Default")
      (node (ref "U$1") (pin "D3") (pinfunction "D3_D3") (pintype "bidirectional"))
    )
    (net (code "118") (name "unconnected-(U$1-PadD4)") (class "Default")
      (node (ref "U$1") (pin "D4") (pinfunction "D4_D4") (pintype "bidirectional"))
    )
    (net (code "119") (name "unconnected-(U$1-PadD7)") (class "Default")
      (node (ref "U$1") (pin "D7") (pinfunction "D7_D7") (pintype "bidirectional"))
    )
    (net (code "120") (name "unconnected-(U$1-PadD8)") (class "Default")
      (node (ref "U$1") (pin "D8") (pinfunction "D8_D8") (pintype "bidirectional"))
    )
    (net (code "121") (name "unconnected-(U$1-PadEN)") (class "Default")
      (node (ref "U$1") (pin "EN") (pinfunction "EN_EN") (pintype "bidirectional"))
    )
    (net (code "122") (name "unconnected-(U$1-PadRST)") (class "Default")
      (node (ref "U$1") (pin "RST") (pinfunction "RST_RST") (pintype "bidirectional"))
    )
    (net (code "123") (name "unconnected-(U$1-PadRX)") (class "Default")
      (node (ref "U$1") (pin "RX") (pinfunction "RX_RX") (pintype "bidirectional"))
    )
    (net (code "124") (name "unconnected-(U$1-PadSD0)") (class "Default")
      (node (ref "U$1") (pin "SD0") (pinfunction "SD0_SD0") (pintype "bidirectional"))
    )
    (net (code "125") (name "unconnected-(U$1-PadSD1)") (class "Default")
      (node (ref "U$1") (pin "SD1") (pinfunction "SD1_SD1") (pintype "bidirectional"))
    )
    (net (code "126") (name "unconnected-(U$1-PadSD2)") (class "Default")
      (node (ref "U$1") (pin "SD2") (pinfunction "SD2_SD2") (pintype "bidirectional"))
    )
    (net (code "127") (name "unconnected-(U$1-PadSD3)") (class "Default")
      (node (ref "U$1") (pin "SD3") (pinfunction "SD3_SD3") (pintype "bidirectional"))
    )
    (net (code "128") (name "unconnected-(U$1-PadTX)") (class "Default")
      (node (ref "U$1") (pin "TX") (pinfunction "TX_TX") (pintype "bidirectional"))
    )
    (net (code "129") (name "unconnected-(U$1-PadVIN)") (class "Default")
      (node (ref "U$1") (pin "VIN") (pinfunction "VIN_VIN") (pintype "bidirectional"))
    )
    (net (code "130") (name "unconnected-(U$1-RSV-PadRSV@0)") (class "Default")
      (node (ref "U$1") (pin "RSV@0") (pinfunction "RSV_RSV@0") (pintype "bidirectional"))
    )
    (net (code "131") (name "unconnected-(U$1-RSV-PadRSV@1)") (class "Default")
      (node (ref "U$1") (pin "RSV@1") (pinfunction "RSV_RSV@1") (pintype "bidirectional"))
    )
  )
)
